# Memory.net
KiCad netlist of a schematic drawn in Altium Designer
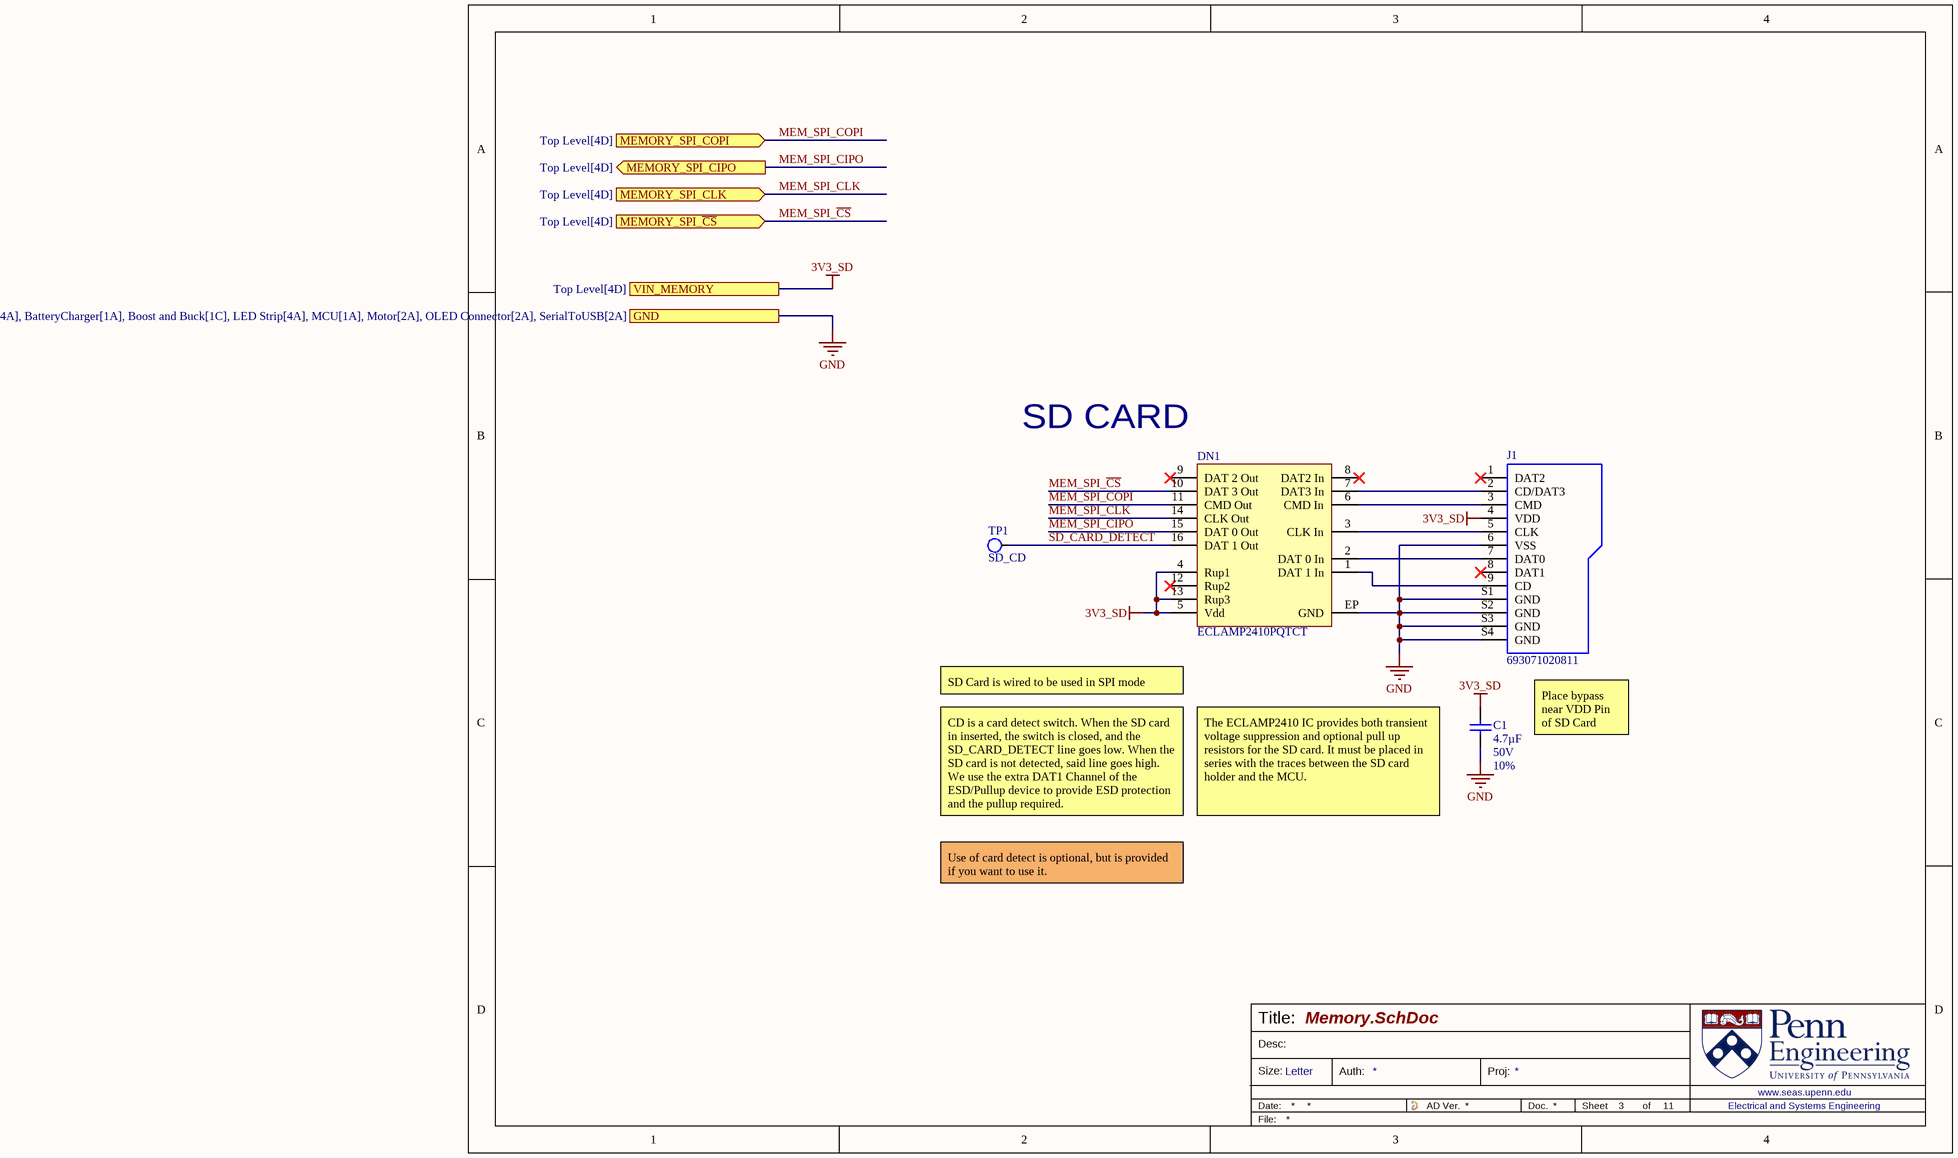
[diagram p0: Memory.SchDoc]

(export (version "E")
  (design (tool "Eeschema 10.0.6"))
  (components
    (comp (ref "C1")
      (value "4.7µF")
      (footprint "0805_CAP")
      (description "Capacitor Surface Mount 0805 Footprint 4.7UF 50V 10% Tolerance Ceramic X5R")
      (fields
        (field (name "VOLTAGE") "50V")
        (field (name "TOLERANCE") "10%")
        (field (name "Comment") "CAP 0805 4.7UF 50V 10% X5R")
      )
      (libsource (lib "University of Pennsylvania (ESE)") (part "cap"))
    )
    (comp (ref "DN1")
      (value "ECLAMP2410PQTCT")
      (footprint "ECLAMP2410PQTCT-Footprint-1")
      (description "Trans Voltage Suppressor Diode, 5V V(RWM), Bidirectional, 7 Element, Silicon with EMI Filter")
      (libsource (lib "University of Pennsylvania (ESE)") (part "ECLAMP2410PQTCT-Symbol-1"))
    )
    (comp (ref "J1")
      (value "693071020811")
      (footprint "693071020811")
      (description "WR-CRD Micro SD Card Connector Push & Push")
      (fields (field (name "PUBLISHER") "Wurth Elektronik"))
      (libsource (lib "University of Pennsylvania (ESE)") (part "CMP-CON-00115-2"))
    )
    (comp (ref "TP1")
      (value "Testpad")
      (footprint "Test PTH 15-30")
      (description "Test Pad/Point (Testpoint, Testpad), for probing")
      (fields (field (name "NETNAME") "SD_CD"))
      (libsource (lib "University of Pennsylvania (ESE)") (part "Test Pad"))
    )
  )
  (nets
    (net (code "1") (name "/MEM_SPI_CIPO") (class "Default")
      (node (ref "DN1") (pin "15") (pinfunction "DAT_0_Out_15") (pintype "passive"))
    )
    (net (code "2") (name "/MEM_SPI_CLK") (class "Default")
      (node (ref "DN1") (pin "14") (pinfunction "CLK_Out_14") (pintype "passive"))
    )
    (net (code "3") (name "/MEM_SPI_COPI") (class "Default")
      (node (ref "DN1") (pin "11") (pinfunction "CMD_Out_11") (pintype "passive"))
    )
    (net (code "4") (name "/MEM_SPI_~{CS}") (class "Default")
      (node (ref "DN1") (pin "10") (pinfunction "DAT_3_Out_10") (pintype "passive"))
    )
    (net (code "5") (name "/SD_CARD_DETECT") (class "Default")
      (node (ref "DN1") (pin "16") (pinfunction "DAT_1_Out_16") (pintype "passive"))
      (node (ref "TP1") (pin "1") (pinfunction "1_1") (pintype "passive"))
    )
    (net (code "6") (name "3V3_SD") (class "Default")
      (node (ref "C1") (pin "2") (pinfunction "2_2") (pintype "passive"))
      (node (ref "DN1") (pin "13") (pinfunction "Rup3_13") (pintype "power_in"))
      (node (ref "DN1") (pin "4") (pinfunction "Rup1_4") (pintype "power_in"))
      (node (ref "DN1") (pin "5") (pinfunction "Vdd_5") (pintype "power_in"))
      (node (ref "J1") (pin "4") (pinfunction "VDD_4") (pintype "passive"))
    )
    (net (code "7") (name "GND") (class "Default")
      (node (ref "C1") (pin "1") (pinfunction "1_1") (pintype "passive"))
      (node (ref "DN1") (pin "EP") (pinfunction "GND_EP") (pintype "power_in"))
      (node (ref "J1") (pin "6") (pinfunction "VSS_6") (pintype "passive"))
      (node (ref "J1") (pin "S1") (pinfunction "GND_S1") (pintype "passive"))
      (node (ref "J1") (pin "S2") (pinfunction "GND_S2") (pintype "passive"))
      (node (ref "J1") (pin "S3") (pinfunction "GND_S3") (pintype "passive"))
      (node (ref "J1") (pin "S4") (pinfunction "GND_S4") (pintype "passive"))
    )
    (net (code "8") (name "Net-(DN1-CLK_In)") (class "Default")
      (node (ref "DN1") (pin "3") (pinfunction "CLK_In_3") (pintype "passive"))
      (node (ref "J1") (pin "5") (pinfunction "CLK_5") (pintype "passive"))
    )
    (net (code "9") (name "Net-(DN1-CMD_In)") (class "Default")
      (node (ref "DN1") (pin "6") (pinfunction "CMD_In_6") (pintype "passive"))
      (node (ref "J1") (pin "3") (pinfunction "CMD_3") (pintype "passive"))
    )
    (net (code "10") (name "Net-(DN1-DAT3_In)") (class "Default")
      (node (ref "DN1") (pin "7") (pinfunction "DAT3_In_7") (pintype "passive"))
      (node (ref "J1") (pin "2") (pinfunction "CD/DAT3_2") (pintype "passive"))
    )
    (net (code "11") (name "Net-(DN1-DAT_0_In)") (class "Default")
      (node (ref "DN1") (pin "2") (pinfunction "DAT_0_In_2") (pintype "passive"))
      (node (ref "J1") (pin "7") (pinfunction "DAT0_7") (pintype "passive"))
    )
    (net (code "12") (name "Net-(DN1-DAT_1_In)") (class "Default")
      (node (ref "DN1") (pin "1") (pinfunction "DAT_1_In_1") (pintype "passive"))
      (node (ref "J1") (pin "9") (pinfunction "CD_9") (pintype "passive"))
    )
    (net (code "13") (name "unconnected-(DN1-DAT2_In-Pad8)") (class "Default")
      (node (ref "DN1") (pin "8") (pinfunction "DAT2_In_8") (pintype "passive+no_connect"))
    )
    (net (code "14") (name "unconnected-(DN1-DAT_2_Out-Pad9)") (class "Default")
      (node (ref "DN1") (pin "9") (pinfunction "DAT_2_Out_9") (pintype "passive+no_connect"))
    )
    (net (code "15") (name "unconnected-(DN1-Rup2-Pad12)") (class "Default")
      (node (ref "DN1") (pin "12") (pinfunction "Rup2_12") (pintype "power_in+no_connect"))
    )
    (net (code "16") (name "unconnected-(J1-DAT1-Pad8)") (class "Default")
      (node (ref "J1") (pin "8") (pinfunction "DAT1_8") (pintype "passive+no_connect"))
    )
    (net (code "17") (name "unconnected-(J1-DAT2-Pad1)") (class "Default")
      (node (ref "J1") (pin "1") (pinfunction "DAT2_1") (pintype "passive+no_connect"))
    )
  )
)
